# Programmer_SCH.net
KiCad netlist of a schematic drawn in Altium Designer
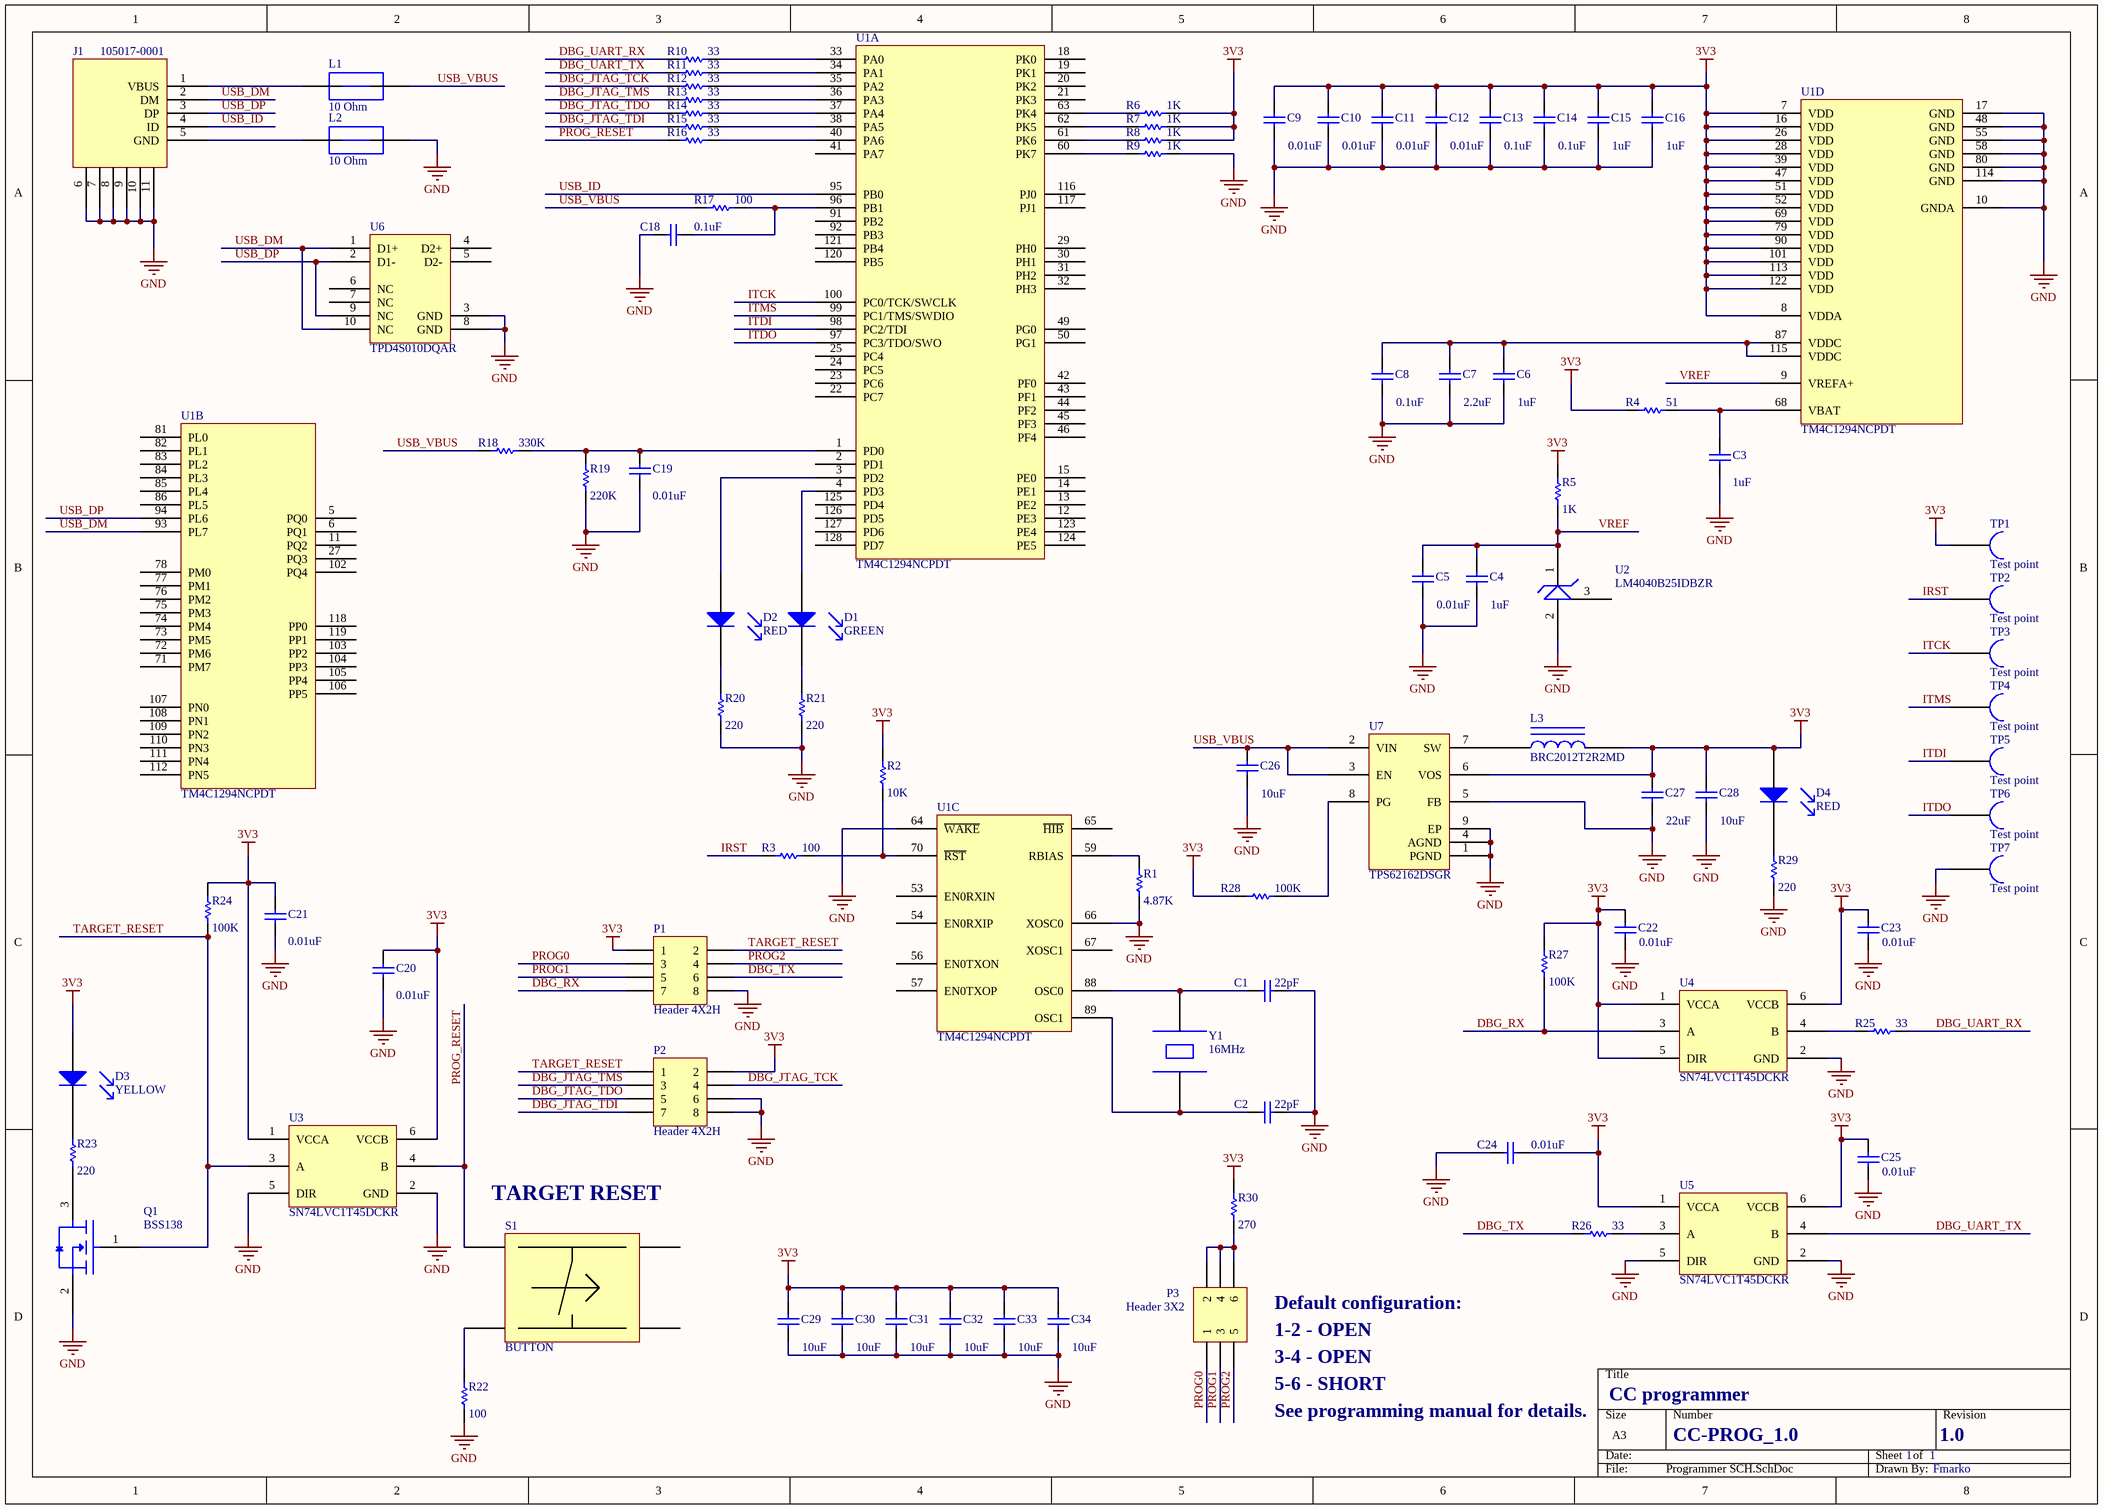
[diagram p0: Programmer SCH.SchDoc]

(export (version "E")
  (design (tool "Eeschema 10.0.6"))
  (components
    (comp (ref "C1")
      (value "22pF")
      (footprint "1608[0603]")
      (description "Capacitor")
      (fields (field (name "PUBLISHER") "Altium Limited"))
      (libsource (lib "Miscellaneous Devices") (part "Cap"))
    )
    (comp (ref "C2")
      (value "22pF")
      (footprint "1608[0603]")
      (description "Capacitor")
      (fields (field (name "PUBLISHER") "Altium Limited"))
      (libsource (lib "Miscellaneous Devices") (part "Cap"))
    )
    (comp (ref "C3")
      (value "1uF")
      (footprint "1608[0603]")
      (description "Capacitor")
      (fields (field (name "PUBLISHER") "Altium Limited"))
      (libsource (lib "Miscellaneous Devices") (part "Cap"))
    )
    (comp (ref "C4")
      (value "1uF")
      (footprint "1608[0603]")
      (description "Capacitor")
      (fields (field (name "PUBLISHER") "Altium Limited"))
      (libsource (lib "Miscellaneous Devices") (part "Cap"))
    )
    (comp (ref "C5")
      (value "0.01uF")
      (footprint "1608[0603]")
      (description "Capacitor")
      (fields (field (name "PUBLISHER") "Altium Limited"))
      (libsource (lib "Miscellaneous Devices") (part "Cap"))
    )
    (comp (ref "C6")
      (value "1uF")
      (footprint "1608[0603]")
      (description "Capacitor")
      (fields (field (name "PUBLISHER") "Altium Limited"))
      (libsource (lib "Miscellaneous Devices") (part "Cap"))
    )
    (comp (ref "C7")
      (value "2.2uF")
      (footprint "1608[0603]")
      (description "Capacitor")
      (fields (field (name "PUBLISHER") "Altium Limited"))
      (libsource (lib "Miscellaneous Devices") (part "Cap"))
    )
    (comp (ref "C8")
      (value "0.1uF")
      (footprint "1608[0603]")
      (description "Capacitor")
      (fields (field (name "PUBLISHER") "Altium Limited"))
      (libsource (lib "Miscellaneous Devices") (part "Cap"))
    )
    (comp (ref "C9")
      (value "0.01uF")
      (footprint "1608[0603]")
      (description "Capacitor")
      (fields (field (name "PUBLISHER") "Altium Limited"))
      (libsource (lib "Miscellaneous Devices") (part "Cap"))
    )
    (comp (ref "C10")
      (value "0.01uF")
      (footprint "1608[0603]")
      (description "Capacitor")
      (fields (field (name "PUBLISHER") "Altium Limited"))
      (libsource (lib "Miscellaneous Devices") (part "Cap"))
    )
    (comp (ref "C11")
      (value "0.01uF")
      (footprint "1608[0603]")
      (description "Capacitor")
      (fields (field (name "PUBLISHER") "Altium Limited"))
      (libsource (lib "Miscellaneous Devices") (part "Cap"))
    )
    (comp (ref "C12")
      (value "0.01uF")
      (footprint "1608[0603]")
      (description "Capacitor")
      (fields (field (name "PUBLISHER") "Altium Limited"))
      (libsource (lib "Miscellaneous Devices") (part "Cap"))
    )
    (comp (ref "C13")
      (value "0.1uF")
      (footprint "1608[0603]")
      (description "Capacitor")
      (fields (field (name "PUBLISHER") "Altium Limited"))
      (libsource (lib "Miscellaneous Devices") (part "Cap"))
    )
    (comp (ref "C14")
      (value "0.1uF")
      (footprint "1608[0603]")
      (description "Capacitor")
      (fields (field (name "PUBLISHER") "Altium Limited"))
      (libsource (lib "Miscellaneous Devices") (part "Cap"))
    )
    (comp (ref "C15")
      (value "1uF")
      (footprint "1608[0603]")
      (description "Capacitor")
      (fields (field (name "PUBLISHER") "Altium Limited"))
      (libsource (lib "Miscellaneous Devices") (part "Cap"))
    )
    (comp (ref "C16")
      (value "1uF")
      (footprint "1608[0603]")
      (description "Capacitor")
      (fields (field (name "PUBLISHER") "Altium Limited"))
      (libsource (lib "Miscellaneous Devices") (part "Cap"))
    )
    (comp (ref "C18")
      (value "0.1uF")
      (footprint "1608[0603]")
      (description "Capacitor")
      (fields (field (name "PUBLISHER") "Altium Limited"))
      (libsource (lib "Miscellaneous Devices") (part "Cap"))
    )
    (comp (ref "C19")
      (value "0.01uF")
      (footprint "1608[0603]")
      (description "Capacitor")
      (fields (field (name "PUBLISHER") "Altium Limited"))
      (libsource (lib "Miscellaneous Devices") (part "Cap"))
    )
    (comp (ref "C20")
      (value "0.01uF")
      (footprint "1608[0603]")
      (description "Capacitor")
      (fields (field (name "PUBLISHER") "Altium Limited"))
      (libsource (lib "Miscellaneous Devices") (part "Cap"))
    )
    (comp (ref "C21")
      (value "0.01uF")
      (footprint "1608[0603]")
      (description "Capacitor")
      (fields (field (name "PUBLISHER") "Altium Limited"))
      (libsource (lib "Miscellaneous Devices") (part "Cap"))
    )
    (comp (ref "C22")
      (value "0.01uF")
      (footprint "1608[0603]")
      (description "Capacitor")
      (fields (field (name "PUBLISHER") "Altium Limited"))
      (libsource (lib "Miscellaneous Devices") (part "Cap"))
    )
    (comp (ref "C23")
      (value "0.01uF")
      (footprint "1608[0603]")
      (description "Capacitor")
      (fields (field (name "PUBLISHER") "Altium Limited"))
      (libsource (lib "Miscellaneous Devices") (part "Cap"))
    )
    (comp (ref "C24")
      (value "0.01uF")
      (footprint "1608[0603]")
      (description "Capacitor")
      (fields (field (name "PUBLISHER") "Altium Limited"))
      (libsource (lib "Miscellaneous Devices") (part "Cap"))
    )
    (comp (ref "C25")
      (value "0.01uF")
      (footprint "1608[0603]")
      (description "Capacitor")
      (fields (field (name "PUBLISHER") "Altium Limited"))
      (libsource (lib "Miscellaneous Devices") (part "Cap"))
    )
    (comp (ref "C26")
      (value "10uF")
      (footprint "1608[0603]")
      (description "Capacitor")
      (fields (field (name "PUBLISHER") "Altium Limited"))
      (libsource (lib "Miscellaneous Devices") (part "Cap"))
    )
    (comp (ref "C27")
      (value "22uF")
      (footprint "1608[0603]")
      (description "Capacitor")
      (fields (field (name "PUBLISHER") "Altium Limited"))
      (libsource (lib "Miscellaneous Devices") (part "Cap"))
    )
    (comp (ref "C28")
      (value "10uF")
      (footprint "1608[0603]")
      (description "Capacitor")
      (fields (field (name "PUBLISHER") "Altium Limited"))
      (libsource (lib "Miscellaneous Devices") (part "Cap"))
    )
    (comp (ref "C29")
      (value "10uF")
      (footprint "C1206")
      (description "Capacitor")
      (fields (field (name "PUBLISHER") "Altium Limited"))
      (libsource (lib "Miscellaneous Devices") (part "Cap"))
    )
    (comp (ref "C30")
      (value "10uF")
      (footprint "C1206")
      (description "Capacitor")
      (fields (field (name "PUBLISHER") "Altium Limited"))
      (libsource (lib "Miscellaneous Devices") (part "Cap"))
    )
    (comp (ref "C31")
      (value "10uF")
      (footprint "C1206")
      (description "Capacitor")
      (fields (field (name "PUBLISHER") "Altium Limited"))
      (libsource (lib "Miscellaneous Devices") (part "Cap"))
    )
    (comp (ref "C32")
      (value "10uF")
      (footprint "C1206")
      (description "Capacitor")
      (fields (field (name "PUBLISHER") "Altium Limited"))
      (libsource (lib "Miscellaneous Devices") (part "Cap"))
    )
    (comp (ref "C33")
      (value "10uF")
      (footprint "C1206")
      (description "Capacitor")
      (fields (field (name "PUBLISHER") "Altium Limited"))
      (libsource (lib "Miscellaneous Devices") (part "Cap"))
    )
    (comp (ref "C34")
      (value "10uF")
      (footprint "C1206")
      (description "Capacitor")
      (fields (field (name "PUBLISHER") "Altium Limited"))
      (libsource (lib "Miscellaneous Devices") (part "Cap"))
    )
    (comp (ref "D1")
      (value "GREEN")
      (footprint "SODFL160X60-2N")
      (description "SML-LX0603GW-TR Green LED, Lumex")
      (libsource (lib "SML-LX0603GW-TR") (part "SML-LX0603GW-TR"))
    )
    (comp (ref "D2")
      (value "RED")
      (footprint "SODFL160X80-2N")
      (description "SML-311UTT86, Red LED diode, ROHM")
      (libsource (lib "SML-311UTT86") (part "SML-311UTT86"))
    )
    (comp (ref "D3")
      (value "YELLOW")
      (footprint "SODFL160X80-2N")
      (description "150060YS75000 Yellow LED diode, Wurth")
      (libsource (lib "150060YS75000") (part "150060YS75000"))
    )
    (comp (ref "D4")
      (value "RED")
      (footprint "SODFL160X80-2N")
      (description "SML-311UTT86, Red LED diode, ROHM")
      (libsource (lib "SML-311UTT86") (part "SML-311UTT86"))
    )
    (comp (ref "J1")
      (value "105017-0001")
      (footprint "105017-0001")
      (description "Micro USB, B type, Molex")
      (libsource (lib "105017-0001") (part "105017-0001"))
    )
    (comp (ref "L1")
      (value "10 Ohm")
      (footprint "INDC1005X06N")
      (description "BLM15AG100SN1D¸SMD filter Inductor, Murata")
      (libsource (lib "BLM15AG100SN1D") (part "BLM15AG100SN1D"))
    )
    (comp (ref "L2")
      (value "10 Ohm")
      (footprint "INDC1005X06N")
      (description "BLM15AG100SN1D¸SMD filter Inductor, Murata")
      (libsource (lib "BLM15AG100SN1D") (part "BLM15AG100SN1D"))
    )
    (comp (ref "L3")
      (value "BRC2012T2R2MD")
      (footprint "INDC2012X10N")
      (description "Wire-Wound chip power inductor, 2012(metric), Taiyo Yuden")
      (libsource (lib "BRC2012T2R2MD") (part "BRC2012T2R2MD"))
    )
    (comp (ref "P1")
      (value "Header 4X2H")
      (footprint "HDR2X4H")
      (description "Header, 4-Pin, Dual row, Right Angle")
      (fields (field (name "PUBLISHER") "Altium Limited"))
      (libsource (lib "Miscellaneous Connectors") (part "Header 4X2H"))
    )
    (comp (ref "P2")
      (value "Header 4X2H")
      (footprint "HDR2X4H")
      (description "Header, 4-Pin, Dual row, Right Angle")
      (fields (field (name "PUBLISHER") "Altium Limited"))
      (libsource (lib "Miscellaneous Connectors") (part "Header 4X2H"))
    )
    (comp (ref "P3")
      (value "Header 3X2")
      (footprint "HDR2X3")
      (description "Header, 3-Pin, Dual row")
      (fields (field (name "PUBLISHER") "Altium Limited"))
      (libsource (lib "Miscellaneous Connectors") (part "Header 3X2"))
    )
    (comp (ref "Q1")
      (value "BSS138")
      (footprint "SOT95P315X120-3N")
      (description ", FAIRCHILD/ON SEMICONDUCTOR")
      (libsource (lib "BSS138") (part "BSS138"))
    )
    (comp (ref "R1")
      (value "4.87K")
      (footprint "1608[0603]")
      (description "Semiconductor Resistor")
      (fields (field (name "PUBLISHER") "Altium Limited"))
      (libsource (lib "Miscellaneous Devices") (part "Res Semi"))
    )
    (comp (ref "R2")
      (value "10K")
      (footprint "1608[0603]")
      (description "Semiconductor Resistor")
      (fields (field (name "PUBLISHER") "Altium Limited"))
      (libsource (lib "Miscellaneous Devices") (part "Res Semi"))
    )
    (comp (ref "R3")
      (value "100")
      (footprint "1608[0603]")
      (description "Semiconductor Resistor")
      (fields (field (name "PUBLISHER") "Altium Limited"))
      (libsource (lib "Miscellaneous Devices") (part "Res Semi"))
    )
    (comp (ref "R4")
      (value "51")
      (footprint "1608[0603]")
      (description "Semiconductor Resistor")
      (fields (field (name "PUBLISHER") "Altium Limited"))
      (libsource (lib "Miscellaneous Devices") (part "Res Semi"))
    )
    (comp (ref "R5")
      (value "1K")
      (footprint "1608[0603]")
      (description "Semiconductor Resistor")
      (fields (field (name "PUBLISHER") "Altium Limited"))
      (libsource (lib "Miscellaneous Devices") (part "Res Semi"))
    )
    (comp (ref "R6")
      (value "1K")
      (footprint "1608[0603]")
      (description "Semiconductor Resistor")
      (fields (field (name "PUBLISHER") "Altium Limited"))
      (libsource (lib "Miscellaneous Devices") (part "Res Semi"))
    )
    (comp (ref "R7")
      (value "1K")
      (footprint "1608[0603]")
      (description "Semiconductor Resistor")
      (fields (field (name "PUBLISHER") "Altium Limited"))
      (libsource (lib "Miscellaneous Devices") (part "Res Semi"))
    )
    (comp (ref "R8")
      (value "1K")
      (footprint "1608[0603]")
      (description "Semiconductor Resistor")
      (fields (field (name "PUBLISHER") "Altium Limited"))
      (libsource (lib "Miscellaneous Devices") (part "Res Semi"))
    )
    (comp (ref "R9")
      (value "1K")
      (footprint "1608[0603]")
      (description "Semiconductor Resistor")
      (fields (field (name "PUBLISHER") "Altium Limited"))
      (libsource (lib "Miscellaneous Devices") (part "Res Semi"))
    )
    (comp (ref "R10")
      (value "33")
      (footprint "1608[0603]")
      (description "Semiconductor Resistor")
      (fields (field (name "PUBLISHER") "Altium Limited"))
      (libsource (lib "Miscellaneous Devices") (part "Res Semi"))
    )
    (comp (ref "R11")
      (value "33")
      (footprint "1608[0603]")
      (description "Semiconductor Resistor")
      (fields (field (name "PUBLISHER") "Altium Limited"))
      (libsource (lib "Miscellaneous Devices") (part "Res Semi"))
    )
    (comp (ref "R12")
      (value "33")
      (footprint "1608[0603]")
      (description "Semiconductor Resistor")
      (fields (field (name "PUBLISHER") "Altium Limited"))
      (libsource (lib "Miscellaneous Devices") (part "Res Semi"))
    )
    (comp (ref "R13")
      (value "33")
      (footprint "1608[0603]")
      (description "Semiconductor Resistor")
      (fields (field (name "PUBLISHER") "Altium Limited"))
      (libsource (lib "Miscellaneous Devices") (part "Res Semi"))
    )
    (comp (ref "R14")
      (value "33")
      (footprint "1608[0603]")
      (description "Semiconductor Resistor")
      (fields (field (name "PUBLISHER") "Altium Limited"))
      (libsource (lib "Miscellaneous Devices") (part "Res Semi"))
    )
    (comp (ref "R15")
      (value "33")
      (footprint "1608[0603]")
      (description "Semiconductor Resistor")
      (fields (field (name "PUBLISHER") "Altium Limited"))
      (libsource (lib "Miscellaneous Devices") (part "Res Semi"))
    )
    (comp (ref "R16")
      (value "33")
      (footprint "1608[0603]")
      (description "Semiconductor Resistor")
      (fields (field (name "PUBLISHER") "Altium Limited"))
      (libsource (lib "Miscellaneous Devices") (part "Res Semi"))
    )
    (comp (ref "R17")
      (value "100")
      (footprint "1608[0603]")
      (description "Semiconductor Resistor")
      (fields (field (name "PUBLISHER") "Altium Limited"))
      (libsource (lib "Miscellaneous Devices") (part "Res Semi"))
    )
    (comp (ref "R18")
      (value "330K")
      (footprint "1608[0603]")
      (description "Semiconductor Resistor")
      (fields (field (name "PUBLISHER") "Altium Limited"))
      (libsource (lib "Miscellaneous Devices") (part "Res Semi"))
    )
    (comp (ref "R19")
      (value "220K")
      (footprint "1608[0603]")
      (description "Semiconductor Resistor")
      (fields (field (name "PUBLISHER") "Altium Limited"))
      (libsource (lib "Miscellaneous Devices") (part "Res Semi"))
    )
    (comp (ref "R20")
      (value "220")
      (footprint "1608[0603]")
      (description "Semiconductor Resistor")
      (fields (field (name "PUBLISHER") "Altium Limited"))
      (libsource (lib "Miscellaneous Devices") (part "Res Semi"))
    )
    (comp (ref "R21")
      (value "220")
      (footprint "1608[0603]")
      (description "Semiconductor Resistor")
      (fields (field (name "PUBLISHER") "Altium Limited"))
      (libsource (lib "Miscellaneous Devices") (part "Res Semi"))
    )
    (comp (ref "R22")
      (value "100")
      (footprint "1608[0603]")
      (description "Semiconductor Resistor")
      (fields (field (name "PUBLISHER") "Altium Limited"))
      (libsource (lib "Miscellaneous Devices") (part "Res Semi"))
    )
    (comp (ref "R23")
      (value "220")
      (footprint "1608[0603]")
      (description "Semiconductor Resistor")
      (fields (field (name "PUBLISHER") "Altium Limited"))
      (libsource (lib "Miscellaneous Devices") (part "Res Semi"))
    )
    (comp (ref "R24")
      (value "100K")
      (footprint "1608[0603]")
      (description "Semiconductor Resistor")
      (fields (field (name "PUBLISHER") "Altium Limited"))
      (libsource (lib "Miscellaneous Devices") (part "Res Semi"))
    )
    (comp (ref "R25")
      (value "33")
      (footprint "1608[0603]")
      (description "Semiconductor Resistor")
      (fields (field (name "PUBLISHER") "Altium Limited"))
      (libsource (lib "Miscellaneous Devices") (part "Res Semi"))
    )
    (comp (ref "R26")
      (value "33")
      (footprint "1608[0603]")
      (description "Semiconductor Resistor")
      (fields (field (name "PUBLISHER") "Altium Limited"))
      (libsource (lib "Miscellaneous Devices") (part "Res Semi"))
    )
    (comp (ref "R27")
      (value "100K")
      (footprint "1608[0603]")
      (description "Semiconductor Resistor")
      (fields (field (name "PUBLISHER") "Altium Limited"))
      (libsource (lib "Miscellaneous Devices") (part "Res Semi"))
    )
    (comp (ref "R28")
      (value "100K")
      (footprint "1608[0603]")
      (description "Semiconductor Resistor")
      (fields (field (name "PUBLISHER") "Altium Limited"))
      (libsource (lib "Miscellaneous Devices") (part "Res Semi"))
    )
    (comp (ref "R29")
      (value "220")
      (footprint "1608[0603]")
      (description "Semiconductor Resistor")
      (fields (field (name "PUBLISHER") "Altium Limited"))
      (libsource (lib "Miscellaneous Devices") (part "Res Semi"))
    )
    (comp (ref "R30")
      (value "270")
      (footprint "1608[0603]")
      (description "Semiconductor Resistor")
      (fields (field (name "PUBLISHER") "Altium Limited"))
      (libsource (lib "Miscellaneous Devices") (part "Res Semi"))
    )
    (comp (ref "S1")
      (value "BUTTON")
      (footprint "PTS645SK43SMTR92LFS")
      (description "PTS645SK43SMTR92LFS Tactile bushbutton, C&K Components")
      (libsource (lib "PTS645SK43SMTR92LFS") (part "PTS645SK43SMTR92LFS"))
    )
    (comp (ref "TP1")
      (value "Test point")
      (footprint "Test_Point_1x1")
      (description "PCB Test Point")
      (libsource (lib "Test point") (part "TP1"))
    )
    (comp (ref "TP2")
      (value "Test point")
      (footprint "Test_Point_1x1")
      (description "PCB Test Point")
      (libsource (lib "Test point") (part "TP1"))
    )
    (comp (ref "TP3")
      (value "Test point")
      (footprint "Test_Point_1x1")
      (description "PCB Test Point")
      (libsource (lib "Test point") (part "TP1"))
    )
    (comp (ref "TP4")
      (value "Test point")
      (footprint "Test_Point_1x1")
      (description "PCB Test Point")
      (libsource (lib "Test point") (part "TP1"))
    )
    (comp (ref "TP5")
      (value "Test point")
      (footprint "Test_Point_1x1")
      (description "PCB Test Point")
      (libsource (lib "Test point") (part "TP1"))
    )
    (comp (ref "TP6")
      (value "Test point")
      (footprint "Test_Point_1x1")
      (description "PCB Test Point")
      (libsource (lib "Test point") (part "TP1"))
    )
    (comp (ref "TP7")
      (value "Test point")
      (footprint "Test_Point_1x1")
      (description "PCB Test Point")
      (libsource (lib "Test point") (part "TP1"))
    )
    (comp (ref "U1")
      (value "TM4C1294NCPDT")
      (footprint "TSQFP40P1600X1600X120-128N")
      (description "TI Tiva C microcontroller, PQFN128")
      (libsource (lib "TM4C1294NCPDT") (part "TM4C1294NCPDT"))
    )
    (comp (ref "U2")
      (value "LM4040B25IDBZR")
      (footprint "SOT95P237X112-3N")
      (description "Precision micropower reference, TI")
      (libsource (lib "LM4040B25IDBZR") (part "LM4040B25IDBZR"))
    )
    (comp (ref "U3")
      (value "SN74LVC1T45DCKR")
      (footprint "TSOP65P210X110-6N")
      (libsource (lib "SN74LVC1T45DCKR") (part "SN74LVC1T45DCKR"))
    )
    (comp (ref "U4")
      (value "SN74LVC1T45DCKR")
      (footprint "TSOP65P210X110-6N")
      (libsource (lib "SN74LVC1T45DCKR") (part "SN74LVC1T45DCKR"))
    )
    (comp (ref "U5")
      (value "SN74LVC1T45DCKR")
      (footprint "TSOP65P210X110-6N")
      (libsource (lib "SN74LVC1T45DCKR") (part "SN74LVC1T45DCKR"))
    )
    (comp (ref "U6")
      (value "TPD4S010DQAR")
      (footprint "SON50P100X55-10N")
      (description "USB ESD Solution, TI")
      (libsource (lib "TPD4S010DQAR") (part "TPD4S010DQAR"))
    )
    (comp (ref "U7")
      (value "TPS62162DSGR")
      (footprint "TPS62162DSGR")
      (description "x 3-V to 17-V, 1-A Step-Down Converters with DCS-Control, TI")
      (libsource (lib "TPS62162DSGR") (part "x 3-V to 17-V, 1-A Step-Down Converters with DCS-Control"))
    )
    (comp (ref "Y1")
      (value "16MHz")
      (footprint "ABM3-16.000MHZ-D2Y-T")
      (description "Crystal 16 MHz, Abracon corporation")
      (libsource (lib "ABM3-16.000MHZ-D2Y-T") (part "ABM3-16.000MHZ-D2Y-T"))
    )
  )
  (nets
    (net (code "1") (name "/DBG_JTAG_TCK") (class "Default")
      (node (ref "P2") (pin "4") (pinfunction "4_4") (pintype "passive"))
      (node (ref "R12") (pin "1") (pinfunction "1_1") (pintype "passive"))
    )
    (net (code "2") (name "/DBG_JTAG_TDI") (class "Default")
      (node (ref "P2") (pin "7") (pinfunction "7_7") (pintype "passive"))
      (node (ref "R15") (pin "1") (pinfunction "1_1") (pintype "passive"))
    )
    (net (code "3") (name "/DBG_JTAG_TDO") (class "Default")
      (node (ref "P2") (pin "5") (pinfunction "5_5") (pintype "passive"))
      (node (ref "R14") (pin "1") (pinfunction "1_1") (pintype "passive"))
    )
    (net (code "4") (name "/DBG_JTAG_TMS") (class "Default")
      (node (ref "P2") (pin "3") (pinfunction "3_3") (pintype "passive"))
      (node (ref "R13") (pin "1") (pinfunction "1_1") (pintype "passive"))
    )
    (net (code "5") (name "/DBG_RX") (class "Default")
      (node (ref "P1") (pin "7") (pinfunction "7_7") (pintype "passive"))
      (node (ref "R27") (pin "2") (pinfunction "2_2") (pintype "passive"))
      (node (ref "U4") (pin "3") (pinfunction "A_3") (pintype "passive"))
    )
    (net (code "6") (name "/DBG_TX") (class "Default")
      (node (ref "P1") (pin "6") (pinfunction "6_6") (pintype "passive"))
      (node (ref "R26") (pin "2") (pinfunction "2_2") (pintype "passive"))
    )
    (net (code "7") (name "/DBG_UART_RX") (class "Default")
      (node (ref "R10") (pin "1") (pinfunction "1_1") (pintype "passive"))
      (node (ref "R25") (pin "1") (pinfunction "1_1") (pintype "passive"))
    )
    (net (code "8") (name "/DBG_UART_TX") (class "Default")
      (node (ref "R11") (pin "1") (pinfunction "1_1") (pintype "passive"))
      (node (ref "U5") (pin "4") (pinfunction "B_4") (pintype "passive"))
    )
    (net (code "9") (name "/IRST") (class "Default")
      (node (ref "R3") (pin "1") (pinfunction "1_1") (pintype "passive"))
      (node (ref "TP2") (pin "1") (pintype "passive"))
    )
    (net (code "10") (name "/ITCK") (class "Default")
      (node (ref "TP3") (pin "1") (pintype "passive"))
      (node (ref "U1") (pin "100") (pinfunction "PC0/TCK/SWCLK_100") (pintype "passive"))
    )
    (net (code "11") (name "/ITDI") (class "Default")
      (node (ref "TP5") (pin "1") (pintype "passive"))
      (node (ref "U1") (pin "98") (pinfunction "PC2/TDI_98") (pintype "passive"))
    )
    (net (code "12") (name "/ITDO") (class "Default")
      (node (ref "TP6") (pin "1") (pintype "passive"))
      (node (ref "U1") (pin "97") (pinfunction "PC3/TDO/SWO_97") (pintype "passive"))
    )
    (net (code "13") (name "/ITMS") (class "Default")
      (node (ref "TP4") (pin "1") (pintype "passive"))
      (node (ref "U1") (pin "99") (pinfunction "PC1/TMS/SWDIO_99") (pintype "passive"))
    )
    (net (code "14") (name "/PROG0") (class "Default")
      (node (ref "P1") (pin "3") (pinfunction "3_3") (pintype "passive"))
      (node (ref "P3") (pin "1") (pinfunction "1_1") (pintype "passive"))
    )
    (net (code "15") (name "/PROG1") (class "Default")
      (node (ref "P1") (pin "5") (pinfunction "5_5") (pintype "passive"))
      (node (ref "P3") (pin "3") (pinfunction "3_3") (pintype "passive"))
    )
    (net (code "16") (name "/PROG2") (class "Default")
      (node (ref "P1") (pin "4") (pinfunction "4_4") (pintype "passive"))
      (node (ref "P3") (pin "5") (pinfunction "5_5") (pintype "passive"))
    )
    (net (code "17") (name "/PROG_RESET") (class "Default")
      (node (ref "R16") (pin "1") (pinfunction "1_1") (pintype "passive"))
      (node (ref "S1") (pin "1") (pintype "passive"))
      (node (ref "U3") (pin "4") (pinfunction "B_4") (pintype "passive"))
    )
    (net (code "18") (name "/TARGET_RESET") (class "Default")
      (node (ref "P1") (pin "2") (pinfunction "2_2") (pintype "passive"))
      (node (ref "P2") (pin "1") (pinfunction "1_1") (pintype "passive"))
      (node (ref "Q1") (pin "1") (pinfunction "G_1") (pintype "passive"))
      (node (ref "R24") (pin "1") (pinfunction "1_1") (pintype "passive"))
      (node (ref "U3") (pin "3") (pinfunction "A_3") (pintype "passive"))
    )
    (net (code "19") (name "/USB_DM") (class "Default")
      (node (ref "J1") (pin "2") (pinfunction "DM_2") (pintype "passive"))
      (node (ref "U1") (pin "93") (pinfunction "PL7_93") (pintype "passive"))
      (node (ref "U6") (pin "1") (pinfunction "D1+_1") (pintype "passive"))
      (node (ref "U6") (pin "10") (pinfunction "NC_10") (pintype "passive"))
    )
    (net (code "20") (name "/USB_DP") (class "Default")
      (node (ref "J1") (pin "3") (pinfunction "DP_3") (pintype "passive"))
      (node (ref "U1") (pin "94") (pinfunction "PL6_94") (pintype "passive"))
      (node (ref "U6") (pin "2") (pinfunction "D1-_2") (pintype "passive"))
      (node (ref "U6") (pin "9") (pinfunction "NC_9") (pintype "passive"))
    )
    (net (code "21") (name "/USB_ID") (class "Default")
      (node (ref "J1") (pin "4") (pinfunction "ID_4") (pintype "passive"))
      (node (ref "U1") (pin "95") (pinfunction "PB0_95") (pintype "passive"))
    )
    (net (code "22") (name "/USB_VBUS") (class "Default")
      (node (ref "C26") (pin "1") (pinfunction "1_1") (pintype "passive"))
      (node (ref "L1") (pin "2") (pintype "passive"))
      (node (ref "R17") (pin "1") (pinfunction "1_1") (pintype "passive"))
      (node (ref "R18") (pin "1") (pinfunction "1_1") (pintype "passive"))
      (node (ref "U7") (pin "2") (pinfunction "VIN_2") (pintype "passive"))
      (node (ref "U7") (pin "3") (pinfunction "EN_3") (pintype "passive"))
    )
    (net (code "23") (name "/VREF") (class "Default")
      (node (ref "C4") (pin "1") (pinfunction "1_1") (pintype "passive"))
      (node (ref "C5") (pin "1") (pinfunction "1_1") (pintype "passive"))
      (node (ref "R5") (pin "1") (pinfunction "1_1") (pintype "passive"))
      (node (ref "U1") (pin "9") (pinfunction "VREFA+_9") (pintype "passive"))
      (node (ref "U2") (pin "1") (pintype "passive"))
    )
    (net (code "24") (name "3V3") (class "Default")
      (node (ref "C10") (pin "1") (pinfunction "1_1") (pintype "passive"))
      (node (ref "C11") (pin "1") (pinfunction "1_1") (pintype "passive"))
      (node (ref "C12") (pin "1") (pinfunction "1_1") (pintype "passive"))
      (node (ref "C13") (pin "1") (pinfunction "1_1") (pintype "passive"))
      (node (ref "C14") (pin "1") (pinfunction "1_1") (pintype "passive"))
      (node (ref "C15") (pin "1") (pinfunction "1_1") (pintype "passive"))
      (node (ref "C16") (pin "1") (pinfunction "1_1") (pintype "passive"))
      (node (ref "C20") (pin "1") (pinfunction "1_1") (pintype "passive"))
      (node (ref "C21") (pin "1") (pinfunction "1_1") (pintype "passive"))
      (node (ref "C22") (pin "1") (pinfunction "1_1") (pintype "passive"))
      (node (ref "C23") (pin "1") (pinfunction "1_1") (pintype "passive"))
      (node (ref "C24") (pin "1") (pinfunction "1_1") (pintype "passive"))
      (node (ref "C25") (pin "1") (pinfunction "1_1") (pintype "passive"))
      (node (ref "C27") (pin "1") (pinfunction "1_1") (pintype "passive"))
      (node (ref "C28") (pin "1") (pinfunction "1_1") (pintype "passive"))
      (node (ref "C29") (pin "1") (pinfunction "1_1") (pintype "passive"))
      (node (ref "C30") (pin "1") (pinfunction "1_1") (pintype "passive"))
      (node (ref "C31") (pin "1") (pinfunction "1_1") (pintype "passive"))
      (node (ref "C32") (pin "1") (pinfunction "1_1") (pintype "passive"))
      (node (ref "C33") (pin "1") (pinfunction "1_1") (pintype "passive"))
      (node (ref "C34") (pin "1") (pinfunction "1_1") (pintype "passive"))
      (node (ref "C9") (pin "1") (pinfunction "1_1") (pintype "passive"))
      (node (ref "D3") (pin "2") (pinfunction "A_2") (pintype "passive"))
      (node (ref "D4") (pin "2") (pinfunction "A_2") (pintype "passive"))
      (node (ref "L3") (pin "2") (pinfunction "2_2") (pintype "passive"))
      (node (ref "P1") (pin "1") (pinfunction "1_1") (pintype "passive"))
      (node (ref "P2") (pin "2") (pinfunction "2_2") (pintype "passive"))
      (node (ref "R2") (pin "2") (pinfunction "2_2") (pintype "passive"))
      (node (ref "R24") (pin "2") (pinfunction "2_2") (pintype "passive"))
      (node (ref "R27") (pin "1") (pinfunction "1_1") (pintype "passive"))
      (node (ref "R28") (pin "2") (pinfunction "2_2") (pintype "passive"))
      (node (ref "R30") (pin "2") (pinfunction "2_2") (pintype "passive"))
      (node (ref "R4") (pin "1") (pinfunction "1_1") (pintype "passive"))
      (node (ref "R5") (pin "2") (pinfunction "2_2") (pintype "passive"))
      (node (ref "R6") (pin "2") (pinfunction "2_2") (pintype "passive"))
      (node (ref "R7") (pin "2") (pinfunction "2_2") (pintype "passive"))
      (node (ref "R8") (pin "2") (pinfunction "2_2") (pintype "passive"))
      (node (ref "TP1") (pin "1") (pintype "passive"))
      (node (ref "U1") (pin "101") (pinfunction "VDD_101") (pintype "passive"))
      (node (ref "U1") (pin "113") (pinfunction "VDD_113") (pintype "passive"))
      (node (ref "U1") (pin "122") (pinfunction "VDD_122") (pintype "passive"))
      (node (ref "U1") (pin "16") (pinfunction "VDD_16") (pintype "passive"))
      (node (ref "U1") (pin "26") (pinfunction "VDD_26") (pintype "passive"))
      (node (ref "U1") (pin "28") (pinfunction "VDD_28") (pintype "passive"))
      (node (ref "U1") (pin "39") (pinfunction "VDD_39") (pintype "passive"))
      (node (ref "U1") (pin "47") (pinfunction "VDD_47") (pintype "passive"))
      (node (ref "U1") (pin "51") (pinfunction "VDD_51") (pintype "passive"))
      (node (ref "U1") (pin "52") (pinfunction "VDD_52") (pintype "passive"))
      (node (ref "U1") (pin "69") (pinfunction "VDD_69") (pintype "passive"))
      (node (ref "U1") (pin "7") (pinfunction "VDD_7") (pintype "passive"))
      (node (ref "U1") (pin "79") (pinfunction "VDD_79") (pintype "passive"))
      (node (ref "U1") (pin "8") (pinfunction "VDDA_8") (pintype "passive"))
      (node (ref "U1") (pin "90") (pinfunction "VDD_90") (pintype "passive"))
      (node (ref "U3") (pin "1") (pinfunction "VCCA_1") (pintype "passive"))
      (node (ref "U3") (pin "6") (pinfunction "VCCB_6") (pintype "passive"))
      (node (ref "U4") (pin "1") (pinfunction "VCCA_1") (pintype "passive"))
      (node (ref "U4") (pin "5") (pinfunction "DIR_5") (pintype "passive"))
      (node (ref "U4") (pin "6") (pinfunction "VCCB_6") (pintype "passive"))
      (node (ref "U5") (pin "1") (pinfunction "VCCA_1") (pintype "passive"))
      (node (ref "U5") (pin "6") (pinfunction "VCCB_6") (pintype "passive"))
      (node (ref "U7") (pin "6") (pinfunction "VOS_6") (pintype "passive"))
    )
    (net (code "25") (name "GND") (class "Default")
      (node (ref "C1") (pin "2") (pinfunction "2_2") (pintype "passive"))
      (node (ref "C10") (pin "2") (pinfunction "2_2") (pintype "passive"))
      (node (ref "C11") (pin "2") (pinfunction "2_2") (pintype "passive"))
      (node (ref "C12") (pin "2") (pinfunction "2_2") (pintype "passive"))
      (node (ref "C13") (pin "2") (pinfunction "2_2") (pintype "passive"))
      (node (ref "C14") (pin "2") (pinfunction "2_2") (pintype "passive"))
      (node (ref "C15") (pin "2") (pinfunction "2_2") (pintype "passive"))
      (node (ref "C16") (pin "2") (pinfunction "2_2") (pintype "passive"))
      (node (ref "C18") (pin "2") (pinfunction "2_2") (pintype "passive"))
      (node (ref "C19") (pin "2") (pinfunction "2_2") (pintype "passive"))
      (node (ref "C2") (pin "2") (pinfunction "2_2") (pintype "passive"))
      (node (ref "C20") (pin "2") (pinfunction "2_2") (pintype "passive"))
      (node (ref "C21") (pin "2") (pinfunction "2_2") (pintype "passive"))
      (node (ref "C22") (pin "2") (pinfunction "2_2") (pintype "passive"))
      (node (ref "C23") (pin "2") (pinfunction "2_2") (pintype "passive"))
      (node (ref "C24") (pin "2") (pinfunction "2_2") (pintype "passive"))
      (node (ref "C25") (pin "2") (pinfunction "2_2") (pintype "passive"))
      (node (ref "C26") (pin "2") (pinfunction "2_2") (pintype "passive"))
      (node (ref "C27") (pin "2") (pinfunction "2_2") (pintype "passive"))
      (node (ref "C28") (pin "2") (pinfunction "2_2") (pintype "passive"))
      (node (ref "C29") (pin "2") (pinfunction "2_2") (pintype "passive"))
      (node (ref "C3") (pin "2") (pinfunction "2_2") (pintype "passive"))
      (node (ref "C30") (pin "2") (pinfunction "2_2") (pintype "passive"))
      (node (ref "C31") (pin "2") (pinfunction "2_2") (pintype "passive"))
      (node (ref "C32") (pin "2") (pinfunction "2_2") (pintype "passive"))
      (node (ref "C33") (pin "2") (pinfunction "2_2") (pintype "passive"))
      (node (ref "C34") (pin "2") (pinfunction "2_2") (pintype "passive"))
      (node (ref "C4") (pin "2") (pinfunction "2_2") (pintype "passive"))
      (node (ref "C5") (pin "2") (pinfunction "2_2") (pintype "passive"))
      (node (ref "C6") (pin "2") (pinfunction "2_2") (pintype "passive"))
      (node (ref "C7") (pin "2") (pinfunction "2_2") (pintype "passive"))
      (node (ref "C8") (pin "2") (pinfunction "2_2") (pintype "passive"))
      (node (ref "C9") (pin "2") (pinfunction "2_2") (pintype "passive"))
      (node (ref "J1") (pin "10") (pintype "passive"))
      (node (ref "J1") (pin "11") (pintype "passive"))
      (node (ref "J1") (pin "6") (pintype "passive"))
      (node (ref "J1") (pin "7") (pintype "passive"))
      (node (ref "J1") (pin "8") (pintype "passive"))
      (node (ref "J1") (pin "9") (pintype "passive"))
      (node (ref "L2") (pin "2") (pintype "passive"))
      (node (ref "P1") (pin "8") (pinfunction "8_8") (pintype "passive"))
      (node (ref "P2") (pin "6") (pinfunction "6_6") (pintype "passive"))
      (node (ref "P2") (pin "8") (pinfunction "8_8") (pintype "passive"))
      (node (ref "Q1") (pin "2") (pinfunction "S_2") (pintype "passive"))
      (node (ref "R1") (pin "1") (pinfunction "1_1") (pintype "passive"))
      (node (ref "R19") (pin "1") (pinfunction "1_1") (pintype "passive"))
      (node (ref "R20") (pin "1") (pinfunction "1_1") (pintype "passive"))
      (node (ref "R21") (pin "1") (pinfunction "1_1") (pintype "passive"))
      (node (ref "R22") (pin "1") (pinfunction "1_1") (pintype "passive"))
      (node (ref "R29") (pin "1") (pinfunction "1_1") (pintype "passive"))
      (node (ref "R9") (pin "2") (pinfunction "2_2") (pintype "passive"))
      (node (ref "TP7") (pin "1") (pintype "passive"))
      (node (ref "U1") (pin "10") (pinfunction "GNDA_10") (pintype "passive"))
      (node (ref "U1") (pin "114") (pinfunction "GND_114") (pintype "passive"))
      (node (ref "U1") (pin "17") (pinfunction "GND_17") (pintype "passive"))
      (node (ref "U1") (pin "48") (pinfunction "GND_48") (pintype "passive"))
      (node (ref "U1") (pin "55") (pinfunction "GND_55") (pintype "passive"))
      (node (ref "U1") (pin "58") (pinfunction "GND_58") (pintype "passive"))
      (node (ref "U1") (pin "64") (pinfunction "~{WAKE}_64") (pintype "passive"))
      (node (ref "U1") (pin "66") (pinfunction "XOSC0_66") (pintype "passive"))
      (node (ref "U1") (pin "80") (pinfunction "GND_80") (pintype "passive"))
      (node (ref "U2") (pin "2") (pintype "passive"))
      (node (ref "U3") (pin "2") (pinfunction "GND_2") (pintype "passive"))
      (node (ref "U3") (pin "5") (pinfunction "DIR_5") (pintype "passive"))
      (node (ref "U4") (pin "2") (pinfunction "GND_2") (pintype "passive"))
      (node (ref "U5") (pin "2") (pinfunction "GND_2") (pintype "passive"))
      (node (ref "U5") (pin "5") (pinfunction "DIR_5") (pintype "passive"))
      (node (ref "U6") (pin "3") (pinfunction "GND_3") (pintype "passive"))
      (node (ref "U6") (pin "8") (pinfunction "GND_8") (pintype "passive"))
      (node (ref "U7") (pin "1") (pinfunction "PGND_1") (pintype "passive"))
      (node (ref "U7") (pin "4") (pinfunction "AGND_4") (pintype "passive"))
      (node (ref "U7") (pin "5") (pinfunction "FB_5") (pintype "passive"))
      (node (ref "U7") (pin "9") (pinfunction "EP_9") (pintype "passive"))
    )
    (net (code "26") (name "Net-(C6-Pad1)") (class "Default")
      (node (ref "C6") (pin "1") (pinfunction "1_1") (pintype "passive"))
      (node (ref "C7") (pin "1") (pinfunction "1_1") (pintype "passive"))
      (node (ref "C8") (pin "1") (pinfunction "1_1") (pintype "passive"))
      (node (ref "U1") (pin "115") (pinfunction "VDDC_115") (pintype "passive"))
      (node (ref "U1") (pin "87") (pinfunction "VDDC_87") (pintype "passive"))
    )
    (net (code "27") (name "Net-(D1-A)") (class "Default")
      (node (ref "D1") (pin "2") (pinfunction "A_2") (pintype "passive"))
      (node (ref "U1") (pin "4") (pinfunction "PD3_4") (pintype "passive"))
    )
    (net (code "28") (name "Net-(D1-C)") (class "Default")
      (node (ref "D1") (pin "1") (pinfunction "C_1") (pintype "passive"))
      (node (ref "R21") (pin "2") (pinfunction "2_2") (pintype "passive"))
    )
    (net (code "29") (name "Net-(D2-A)") (class "Default")
      (node (ref "D2") (pin "2") (pinfunction "A_2") (pintype "passive"))
      (node (ref "U1") (pin "3") (pinfunction "PD2_3") (pintype "passive"))
    )
    (net (code "30") (name "Net-(D2-C)") (class "Default")
      (node (ref "D2") (pin "1") (pinfunction "C_1") (pintype "passive"))
      (node (ref "R20") (pin "2") (pinfunction "2_2") (pintype "passive"))
    )
    (net (code "31") (name "Net-(D3-C)") (class "Default")
      (node (ref "D3") (pin "1") (pinfunction "C_1") (pintype "passive"))
      (node (ref "R23") (pin "2") (pinfunction "2_2") (pintype "passive"))
    )
    (net (code "32") (name "Net-(D4-C)") (class "Default")
      (node (ref "D4") (pin "1") (pinfunction "C_1") (pintype "passive"))
      (node (ref "R29") (pin "2") (pinfunction "2_2") (pintype "passive"))
    )
    (net (code "33") (name "Net-(J1-GND)") (class "Default")
      (node (ref "J1") (pin "5") (pinfunction "GND_5") (pintype "passive"))
      (node (ref "L2") (pin "1") (pintype "passive"))
    )
    (net (code "34") (name "Net-(J1-VBUS)") (class "Default")
      (node (ref "J1") (pin "1") (pinfunction "VBUS_1") (pintype "passive"))
      (node (ref "L1") (pin "1") (pintype "passive"))
    )
    (net (code "35") (name "Net-(P3-Pad2)") (class "Default")
      (node (ref "P3") (pin "2") (pinfunction "2_2") (pintype "passive"))
      (node (ref "P3") (pin "4") (pinfunction "4_4") (pintype "passive"))
      (node (ref "P3") (pin "6") (pinfunction "6_6") (pintype "passive"))
      (node (ref "R30") (pin "1") (pinfunction "1_1") (pintype "passive"))
    )
    (net (code "36") (name "Net-(Q1-D)") (class "Default")
      (node (ref "Q1") (pin "3") (pinfunction "D_3") (pintype "passive"))
      (node (ref "R23") (pin "1") (pinfunction "1_1") (pintype "passive"))
    )
    (net (code "37") (name "Net-(R22-Pad2)") (class "Default")
      (node (ref "R22") (pin "2") (pinfunction "2_2") (pintype "passive"))
      (node (ref "S1") (pin "3") (pintype "passive"))
    )
    (net (code "38") (name "Net-(U1A-PA0)") (class "Default")
      (node (ref "R10") (pin "2") (pinfunction "2_2") (pintype "passive"))
      (node (ref "U1") (pin "33") (pinfunction "PA0_33") (pintype "passive"))
    )
    (net (code "39") (name "Net-(U1A-PA1)") (class "Default")
      (node (ref "R11") (pin "2") (pinfunction "2_2") (pintype "passive"))
      (node (ref "U1") (pin "34") (pinfunction "PA1_34") (pintype "passive"))
    )
    (net (code "40") (name "Net-(U1A-PA2)") (class "Default")
      (node (ref "R12") (pin "2") (pinfunction "2_2") (pintype "passive"))
      (node (ref "U1") (pin "35") (pinfunction "PA2_35") (pintype "passive"))
    )
    (net (code "41") (name "Net-(U1A-PA3)") (class "Default")
      (node (ref "R13") (pin "2") (pinfunction "2_2") (pintype "passive"))
      (node (ref "U1") (pin "36") (pinfunction "PA3_36") (pintype "passive"))
    )
    (net (code "42") (name "Net-(U1A-PA4)") (class "Default")
      (node (ref "R14") (pin "2") (pinfunction "2_2") (pintype "passive"))
      (node (ref "U1") (pin "37") (pinfunction "PA4_37") (pintype "passive"))
    )
    (net (code "43") (name "Net-(U1A-PA5)") (class "Default")
      (node (ref "R15") (pin "2") (pinfunction "2_2") (pintype "passive"))
      (node (ref "U1") (pin "38") (pinfunction "PA5_38") (pintype "passive"))
    )
    (net (code "44") (name "Net-(U1A-PA6)") (class "Default")
      (node (ref "R16") (pin "2") (pinfunction "2_2") (pintype "passive"))
      (node (ref "U1") (pin "40") (pinfunction "PA6_40") (pintype "passive"))
    )
    (net (code "45") (name "Net-(U1A-PB1)") (class "Default")
      (node (ref "C18") (pin "1") (pinfunction "1_1") (pintype "passive"))
      (node (ref "R17") (pin "2") (pinfunction "2_2") (pintype "passive"))
      (node (ref "U1") (pin "96") (pinfunction "PB1_96") (pintype "passive"))
    )
    (net (code "46") (name "Net-(U1A-PD0)") (class "Default")
      (node (ref "C19") (pin "1") (pinfunction "1_1") (pintype "passive"))
      (node (ref "R18") (pin "2") (pinfunction "2_2") (pintype "passive"))
      (node (ref "R19") (pin "2") (pinfunction "2_2") (pintype "passive"))
      (node (ref "U1") (pin "1") (pinfunction "PD0_1") (pintype "passive"))
    )
    (net (code "47") (name "Net-(U1A-PK4)") (class "Default")
      (node (ref "R6") (pin "1") (pinfunction "1_1") (pintype "passive"))
      (node (ref "U1") (pin "63") (pinfunction "PK4_63") (pintype "passive"))
    )
    (net (code "48") (name "Net-(U1A-PK5)") (class "Default")
      (node (ref "R7") (pin "1") (pinfunction "1_1") (pintype "passive"))
      (node (ref "U1") (pin "62") (pinfunction "PK5_62") (pintype "passive"))
    )
    (net (code "49") (name "Net-(U1A-PK6)") (class "Default")
      (node (ref "R8") (pin "1") (pinfunction "1_1") (pintype "passive"))
      (node (ref "U1") (pin "61") (pinfunction "PK6_61") (pintype "passive"))
    )
    (net (code "50") (name "Net-(U1A-PK7)") (class "Default")
      (node (ref "R9") (pin "1") (pinfunction "1_1") (pintype "passive"))
      (node (ref "U1") (pin "60") (pinfunction "PK7_60") (pintype "passive"))
    )
    (net (code "51") (name "Net-(U1C-OSC0)") (class "Default")
      (node (ref "C1") (pin "1") (pinfunction "1_1") (pintype "passive"))
      (node (ref "U1") (pin "88") (pinfunction "OSC0_88") (pintype "passive"))
      (node (ref "Y1") (pin "2") (pintype "passive"))
    )
    (net (code "52") (name "Net-(U1C-OSC1)") (class "Default")
      (node (ref "C2") (pin "1") (pinfunction "1_1") (pintype "passive"))
      (node (ref "U1") (pin "89") (pinfunction "OSC1_89") (pintype "passive"))
      (node (ref "Y1") (pin "1") (pintype "passive"))
    )
    (net (code "53") (name "Net-(U1C-RBIAS)") (class "Default")
      (node (ref "R1") (pin "2") (pinfunction "2_2") (pintype "passive"))
      (node (ref "U1") (pin "59") (pinfunction "RBIAS_59") (pintype "passive"))
    )
    (net (code "54") (name "Net-(U1C-~{RST})") (class "Default")
      (node (ref "R2") (pin "1") (pinfunction "1_1") (pintype "passive"))
      (node (ref "R3") (pin "2") (pinfunction "2_2") (pintype "passive"))
      (node (ref "U1") (pin "70") (pinfunction "~{RST}_70") (pintype "passive"))
    )
    (net (code "55") (name "Net-(U1D-VBAT)") (class "Default")
      (node (ref "C3") (pin "1") (pinfunction "1_1") (pintype "passive"))
      (node (ref "R4") (pin "2") (pinfunction "2_2") (pintype "passive"))
      (node (ref "U1") (pin "68") (pinfunction "VBAT_68") (pintype "passive"))
    )
    (net (code "56") (name "Net-(U4-B)") (class "Default")
      (node (ref "R25") (pin "2") (pinfunction "2_2") (pintype "passive"))
      (node (ref "U4") (pin "4") (pinfunction "B_4") (pintype "passive"))
    )
    (net (code "57") (name "Net-(U5-A)") (class "Default")
      (node (ref "R26") (pin "1") (pinfunction "1_1") (pintype "passive"))
      (node (ref "U5") (pin "3") (pinfunction "A_3") (pintype "passive"))
    )
    (net (code "58") (name "Net-(U7-PG)") (class "Default")
      (node (ref "R28") (pin "1") (pinfunction "1_1") (pintype "passive"))
      (node (ref "U7") (pin "8") (pinfunction "PG_8") (pintype "passive"))
    )
    (net (code "59") (name "Net-(U7-SW)") (class "Default")
      (node (ref "L3") (pin "1") (pinfunction "1_1") (pintype "passive"))
      (node (ref "U7") (pin "7") (pinfunction "SW_7") (pintype "passive"))
    )
    (net (code "60") (name "unconnected-(S1-Pad2)") (class "Default")
      (node (ref "S1") (pin "2") (pintype "passive"))
    )
    (net (code "61") (name "unconnected-(S1-Pad4)") (class "Default")
      (node (ref "S1") (pin "4") (pintype "passive"))
    )
    (net (code "62") (name "unconnected-(U1A-PA7-Pad41)") (class "Default")
      (node (ref "U1") (pin "41") (pinfunction "PA7_41") (pintype "passive"))
    )
    (net (code "63") (name "unconnected-(U1A-PB2-Pad91)") (class "Default")
      (node (ref "U1") (pin "91") (pinfunction "PB2_91") (pintype "passive"))
    )
    (net (code "64") (name "unconnected-(U1A-PB3-Pad92)") (class "Default")
      (node (ref "U1") (pin "92") (pinfunction "PB3_92") (pintype "passive"))
    )
    (net (code "65") (name "unconnected-(U1A-PB4-Pad121)") (class "Default")
      (node (ref "U1") (pin "121") (pinfunction "PB4_121") (pintype "passive"))
    )
    (net (code "66") (name "unconnected-(U1A-PB5-Pad120)") (class "Default")
      (node (ref "U1") (pin "120") (pinfunction "PB5_120") (pintype "passive"))
    )
    (net (code "67") (name "unconnected-(U1A-PC4-Pad25)") (class "Default")
      (node (ref "U1") (pin "25") (pinfunction "PC4_25") (pintype "passive"))
    )
    (net (code "68") (name "unconnected-(U1A-PC5-Pad24)") (class "Default")
      (node (ref "U1") (pin "24") (pinfunction "PC5_24") (pintype "passive"))
    )
    (net (code "69") (name "unconnected-(U1A-PC6-Pad23)") (class "Default")
      (node (ref "U1") (pin "23") (pinfunction "PC6_23") (pintype "passive"))
    )
    (net (code "70") (name "unconnected-(U1A-PC7-Pad22)") (class "Default")
      (node (ref "U1") (pin "22") (pinfunction "PC7_22") (pintype "passive"))
    )
    (net (code "71") (name "unconnected-(U1A-PD1-Pad2)") (class "Default")
      (node (ref "U1") (pin "2") (pinfunction "PD1_2") (pintype "passive"))
    )
    (net (code "72") (name "unconnected-(U1A-PD4-Pad125)") (class "Default")
      (node (ref "U1") (pin "125") (pinfunction "PD4_125") (pintype "passive"))
    )
    (net (code "73") (name "unconnected-(U1A-PD5-Pad126)") (class "Default")
      (node (ref "U1") (pin "126") (pinfunction "PD5_126") (pintype "passive"))
    )
    (net (code "74") (name "unconnected-(U1A-PD6-Pad127)") (class "Default")
      (node (ref "U1") (pin "127") (pinfunction "PD6_127") (pintype "passive"))
    )
    (net (code "75") (name "unconnected-(U1A-PD7-Pad128)") (class "Default")
      (node (ref "U1") (pin "128") (pinfunction "PD7_128") (pintype "passive"))
    )
    (net (code "76") (name "unconnected-(U1A-PE0-Pad15)") (class "Default")
      (node (ref "U1") (pin "15") (pinfunction "PE0_15") (pintype "passive"))
    )
    (net (code "77") (name "unconnected-(U1A-PE1-Pad14)") (class "Default")
      (node (ref "U1") (pin "14") (pinfunction "PE1_14") (pintype "passive"))
    )
    (net (code "78") (name "unconnected-(U1A-PE2-Pad13)") (class "Default")
      (node (ref "U1") (pin "13") (pinfunction "PE2_13") (pintype "passive"))
    )
    (net (code "79") (name "unconnected-(U1A-PE3-Pad12)") (class "Default")
      (node (ref "U1") (pin "12") (pinfunction "PE3_12") (pintype "passive"))
    )
    (net (code "80") (name "unconnected-(U1A-PE4-Pad123)") (class "Default")
      (node (ref "U1") (pin "123") (pinfunction "PE4_123") (pintype "passive"))
    )
    (net (code "81") (name "unconnected-(U1A-PE5-Pad124)") (class "Default")
      (node (ref "U1") (pin "124") (pinfunction "PE5_124") (pintype "passive"))
    )
    (net (code "82") (name "unconnected-(U1A-PF0-Pad42)") (class "Default")
      (node (ref "U1") (pin "42") (pinfunction "PF0_42") (pintype "passive"))
    )
    (net (code "83") (name "unconnected-(U1A-PF1-Pad43)") (class "Default")
      (node (ref "U1") (pin "43") (pinfunction "PF1_43") (pintype "passive"))
    )
    (net (code "84") (name "unconnected-(U1A-PF2-Pad44)") (class "Default")
      (node (ref "U1") (pin "44") (pinfunction "PF2_44") (pintype "passive"))
    )
    (net (code "85") (name "unconnected-(U1A-PF3-Pad45)") (class "Default")
      (node (ref "U1") (pin "45") (pinfunction "PF3_45") (pintype "passive"))
    )
    (net (code "86") (name "unconnected-(U1A-PF4-Pad46)") (class "Default")
      (node (ref "U1") (pin "46") (pinfunction "PF4_46") (pintype "passive"))
    )
    (net (code "87") (name "unconnected-(U1A-PG0-Pad49)") (class "Default")
      (node (ref "U1") (pin "49") (pinfunction "PG0_49") (pintype "passive"))
    )
    (net (code "88") (name "unconnected-(U1A-PG1-Pad50)") (class "Default")
      (node (ref "U1") (pin "50") (pinfunction "PG1_50") (pintype "passive"))
    )
    (net (code "89") (name "unconnected-(U1A-PH0-Pad29)") (class "Default")
      (node (ref "U1") (pin "29") (pinfunction "PH0_29") (pintype "passive"))
    )
    (net (code "90") (name "unconnected-(U1A-PH1-Pad30)") (class "Default")
      (node (ref "U1") (pin "30") (pinfunction "PH1_30") (pintype "passive"))
    )
    (net (code "91") (name "unconnected-(U1A-PH2-Pad31)") (class "Default")
      (node (ref "U1") (pin "31") (pinfunction "PH2_31") (pintype "passive"))
    )
    (net (code "92") (name "unconnected-(U1A-PH3-Pad32)") (class "Default")
      (node (ref "U1") (pin "32") (pinfunction "PH3_32") (pintype "passive"))
    )
    (net (code "93") (name "unconnected-(U1A-PJ0-Pad116)") (class "Default")
      (node (ref "U1") (pin "116") (pinfunction "PJ0_116") (pintype "passive"))
    )
    (net (code "94") (name "unconnected-(U1A-PJ1-Pad117)") (class "Default")
      (node (ref "U1") (pin "117") (pinfunction "PJ1_117") (pintype "passive"))
    )
    (net (code "95") (name "unconnected-(U1A-PK0-Pad18)") (class "Default")
      (node (ref "U1") (pin "18") (pinfunction "PK0_18") (pintype "passive"))
    )
    (net (code "96") (name "unconnected-(U1A-PK1-Pad19)") (class "Default")
      (node (ref "U1") (pin "19") (pinfunction "PK1_19") (pintype "passive"))
    )
    (net (code "97") (name "unconnected-(U1A-PK2-Pad20)") (class "Default")
      (node (ref "U1") (pin "20") (pinfunction "PK2_20") (pintype "passive"))
    )
    (net (code "98") (name "unconnected-(U1A-PK3-Pad21)") (class "Default")
      (node (ref "U1") (pin "21") (pinfunction "PK3_21") (pintype "passive"))
    )
    (net (code "99") (name "unconnected-(U1B-PL0-Pad81)") (class "Default")
      (node (ref "U1") (pin "81") (pinfunction "PL0_81") (pintype "passive"))
    )
    (net (code "100") (name "unconnected-(U1B-PL1-Pad82)") (class "Default")
      (node (ref "U1") (pin "82") (pinfunction "PL1_82") (pintype "passive"))
    )
    (net (code "101") (name "unconnected-(U1B-PL2-Pad83)") (class "Default")
      (node (ref "U1") (pin "83") (pinfunction "PL2_83") (pintype "passive"))
    )
    (net (code "102") (name "unconnected-(U1B-PL3-Pad84)") (class "Default")
      (node (ref "U1") (pin "84") (pinfunction "PL3_84") (pintype "passive"))
    )
    (net (code "103") (name "unconnected-(U1B-PL4-Pad85)") (class "Default")
      (node (ref "U1") (pin "85") (pinfunction "PL4_85") (pintype "passive"))
    )
    (net (code "104") (name "unconnected-(U1B-PL5-Pad86)") (class "Default")
      (node (ref "U1") (pin "86") (pinfunction "PL5_86") (pintype "passive"))
    )
    (net (code "105") (name "unconnected-(U1B-PM0-Pad78)") (class "Default")
      (node (ref "U1") (pin "78") (pinfunction "PM0_78") (pintype "passive"))
    )
    (net (code "106") (name "unconnected-(U1B-PM1-Pad77)") (class "Default")
      (node (ref "U1") (pin "77") (pinfunction "PM1_77") (pintype "passive"))
    )
    (net (code "107") (name "unconnected-(U1B-PM2-Pad76)") (class "Default")
      (node (ref "U1") (pin "76") (pinfunction "PM2_76") (pintype "passive"))
    )
    (net (code "108") (name "unconnected-(U1B-PM3-Pad75)") (class "Default")
      (node (ref "U1") (pin "75") (pinfunction "PM3_75") (pintype "passive"))
    )
    (net (code "109") (name "unconnected-(U1B-PM4-Pad74)") (class "Default")
      (node (ref "U1") (pin "74") (pinfunction "PM4_74") (pintype "passive"))
    )
    (net (code "110") (name "unconnected-(U1B-PM5-Pad73)") (class "Default")
      (node (ref "U1") (pin "73") (pinfunction "PM5_73") (pintype "passive"))
    )
    (net (code "111") (name "unconnected-(U1B-PM6-Pad72)") (class "Default")
      (node (ref "U1") (pin "72") (pinfunction "PM6_72") (pintype "passive"))
    )
    (net (code "112") (name "unconnected-(U1B-PM7-Pad71)") (class "Default")
      (node (ref "U1") (pin "71") (pinfunction "PM7_71") (pintype "passive"))
    )
    (net (code "113") (name "unconnected-(U1B-PN0-Pad107)") (class "Default")
      (node (ref "U1") (pin "107") (pinfunction "PN0_107") (pintype "passive"))
    )
    (net (code "114") (name "unconnected-(U1B-PN1-Pad108)") (class "Default")
      (node (ref "U1") (pin "108") (pinfunction "PN1_108") (pintype "passive"))
    )
    (net (code "115") (name "unconnected-(U1B-PN2-Pad109)") (class "Default")
      (node (ref "U1") (pin "109") (pinfunction "PN2_109") (pintype "passive"))
    )
    (net (code "116") (name "unconnected-(U1B-PN3-Pad110)") (class "Default")
      (node (ref "U1") (pin "110") (pinfunction "PN3_110") (pintype "passive"))
    )
    (net (code "117") (name "unconnected-(U1B-PN4-Pad111)") (class "Default")
      (node (ref "U1") (pin "111") (pinfunction "PN4_111") (pintype "passive"))
    )
    (net (code "118") (name "unconnected-(U1B-PN5-Pad112)") (class "Default")
      (node (ref "U1") (pin "112") (pinfunction "PN5_112") (pintype "passive"))
    )
    (net (code "119") (name "unconnected-(U1B-PP0-Pad118)") (class "Default")
      (node (ref "U1") (pin "118") (pinfunction "PP0_118") (pintype "passive"))
    )
    (net (code "120") (name "unconnected-(U1B-PP1-Pad119)") (class "Default")
      (node (ref "U1") (pin "119") (pinfunction "PP1_119") (pintype "passive"))
    )
    (net (code "121") (name "unconnected-(U1B-PP2-Pad103)") (class "Default")
      (node (ref "U1") (pin "103") (pinfunction "PP2_103") (pintype "passive"))
    )
    (net (code "122") (name "unconnected-(U1B-PP3-Pad104)") (class "Default")
      (node (ref "U1") (pin "104") (pinfunction "PP3_104") (pintype "passive"))
    )
    (net (code "123") (name "unconnected-(U1B-PP4-Pad105)") (class "Default")
      (node (ref "U1") (pin "105") (pinfunction "PP4_105") (pintype "passive"))
    )
    (net (code "124") (name "unconnected-(U1B-PP5-Pad106)") (class "Default")
      (node (ref "U1") (pin "106") (pinfunction "PP5_106") (pintype "passive"))
    )
    (net (code "125") (name "unconnected-(U1B-PQ0-Pad5)") (class "Default")
      (node (ref "U1") (pin "5") (pinfunction "PQ0_5") (pintype "passive"))
    )
    (net (code "126") (name "unconnected-(U1B-PQ1-Pad6)") (class "Default")
      (node (ref "U1") (pin "6") (pinfunction "PQ1_6") (pintype "passive"))
    )
    (net (code "127") (name "unconnected-(U1B-PQ2-Pad11)") (class "Default")
      (node (ref "U1") (pin "11") (pinfunction "PQ2_11") (pintype "passive"))
    )
    (net (code "128") (name "unconnected-(U1B-PQ3-Pad27)") (class "Default")
      (node (ref "U1") (pin "27") (pinfunction "PQ3_27") (pintype "passive"))
    )
    (net (code "129") (name "unconnected-(U1B-PQ4-Pad102)") (class "Default")
      (node (ref "U1") (pin "102") (pinfunction "PQ4_102") (pintype "passive"))
    )
    (net (code "130") (name "unconnected-(U1C-EN0RXIN-Pad53)") (class "Default")
      (node (ref "U1") (pin "53") (pinfunction "EN0RXIN_53") (pintype "passive"))
    )
    (net (code "131") (name "unconnected-(U1C-EN0RXIP-Pad54)") (class "Default")
      (node (ref "U1") (pin "54") (pinfunction "EN0RXIP_54") (pintype "passive"))
    )
    (net (code "132") (name "unconnected-(U1C-EN0TXON-Pad56)") (class "Default")
      (node (ref "U1") (pin "56") (pinfunction "EN0TXON_56") (pintype "passive"))
    )
    (net (code "133") (name "unconnected-(U1C-EN0TXOP-Pad57)") (class "Default")
      (node (ref "U1") (pin "57") (pinfunction "EN0TXOP_57") (pintype "passive"))
    )
    (net (code "134") (name "unconnected-(U1C-XOSC1-Pad67)") (class "Default")
      (node (ref "U1") (pin "67") (pinfunction "XOSC1_67") (pintype "passive"))
    )
    (net (code "135") (name "unconnected-(U1C-~{HIB}-Pad65)") (class "Default")
      (node (ref "U1") (pin "65") (pinfunction "~{HIB}_65") (pintype "passive"))
    )
    (net (code "136") (name "unconnected-(U2-Pad3)") (class "Default")
      (node (ref "U2") (pin "3") (pintype "passive"))
    )
    (net (code "137") (name "unconnected-(U6-D2+-Pad4)") (class "Default")
      (node (ref "U6") (pin "4") (pinfunction "D2+_4") (pintype "passive"))
    )
    (net (code "138") (name "unconnected-(U6-D2--Pad5)") (class "Default")
      (node (ref "U6") (pin "5") (pinfunction "D2-_5") (pintype "passive"))
    )
    (net (code "139") (name "unconnected-(U6-NC-Pad6)") (class "Default")
      (node (ref "U6") (pin "6") (pinfunction "NC_6") (pintype "passive"))
    )
    (net (code "140") (name "unconnected-(U6-NC-Pad7)") (class "Default")
      (node (ref "U6") (pin "7") (pinfunction "NC_7") (pintype "passive"))
    )
  )
)
